# HOMADOS.net
KiCad netlist of a schematic drawn in EAGLE
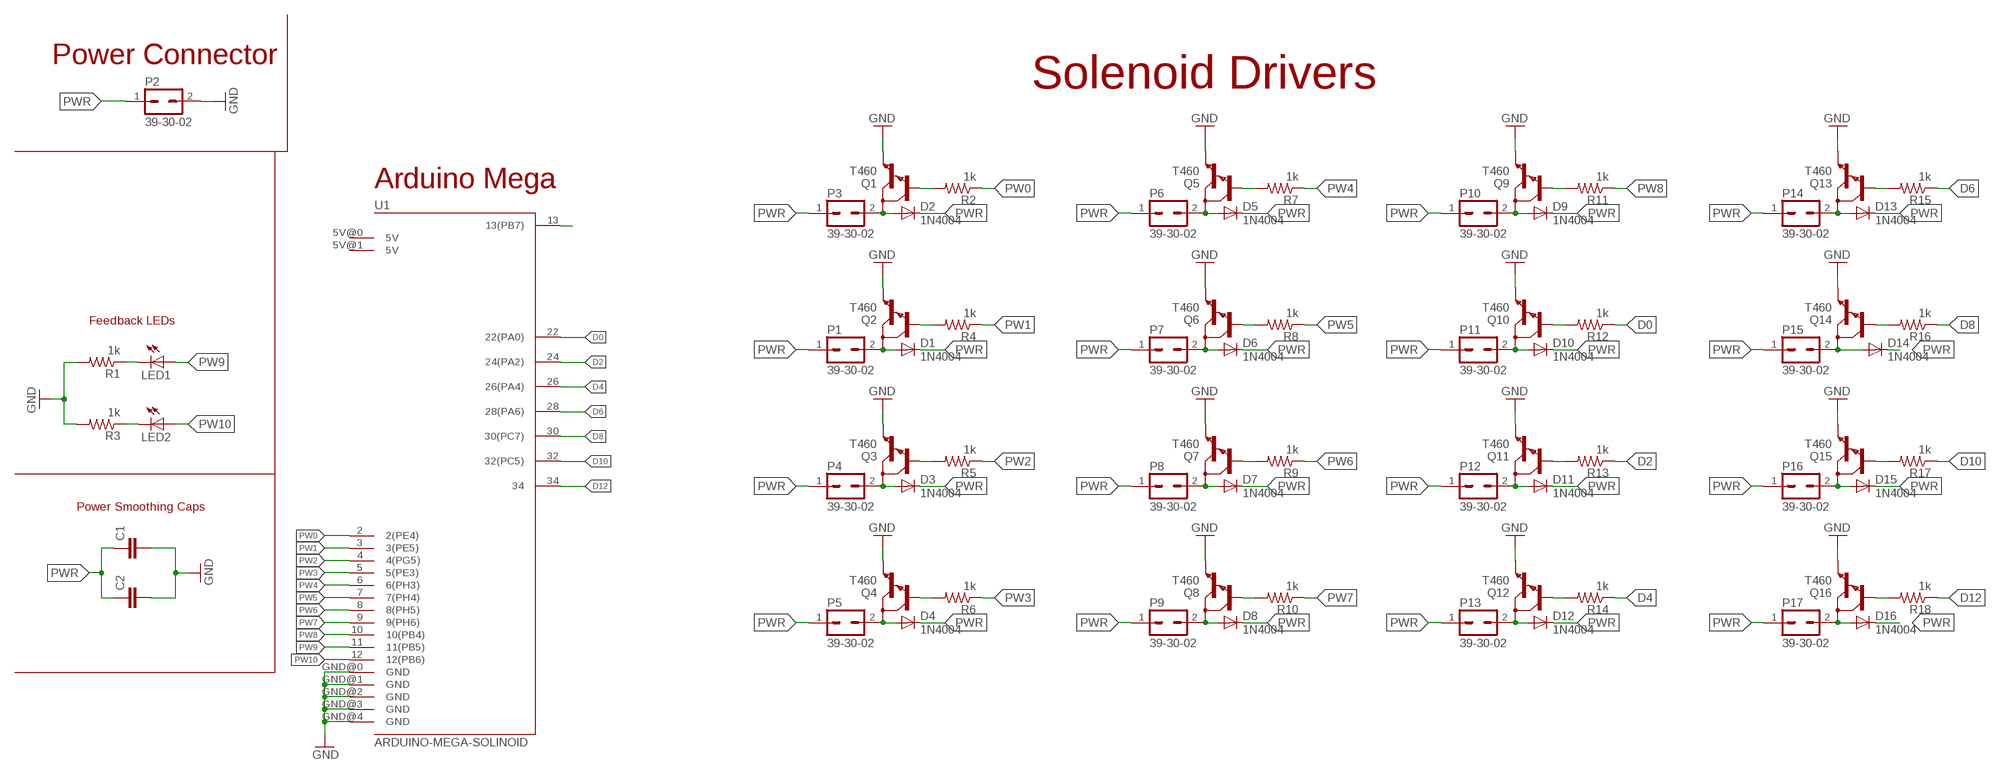
[diagram p0: schematic, sheet 1]

(export (version "E")
  (design (tool "Eeschema 10.0.6"))
  (components
    (comp (ref "C1")
      (value "CAPPTH1")
      (footprint "eagle-import:CAP-PTH-5MM")
      (libsource (lib "eagle-import") (part "CAPPTH1"))
    )
    (comp (ref "C2")
      (value "CAPPTH3")
      (footprint "eagle-import:CAP-PTH-LARGE")
      (libsource (lib "eagle-import") (part "CAPPTH3"))
    )
    (comp (ref "D1")
      (value "1N4004")
      (footprint "eagle-import:DO41-10")
      (libsource (lib "eagle-import") (part "1N4004"))
    )
    (comp (ref "D2")
      (value "1N4004")
      (footprint "eagle-import:DO41-10")
      (libsource (lib "eagle-import") (part "1N4004"))
    )
    (comp (ref "D3")
      (value "1N4004")
      (footprint "eagle-import:DO41-10")
      (libsource (lib "eagle-import") (part "1N4004"))
    )
    (comp (ref "D4")
      (value "1N4004")
      (footprint "eagle-import:DO41-10")
      (libsource (lib "eagle-import") (part "1N4004"))
    )
    (comp (ref "D5")
      (value "1N4004")
      (footprint "eagle-import:DO41-10")
      (libsource (lib "eagle-import") (part "1N4004"))
    )
    (comp (ref "D6")
      (value "1N4004")
      (footprint "eagle-import:DO41-10")
      (libsource (lib "eagle-import") (part "1N4004"))
    )
    (comp (ref "D7")
      (value "1N4004")
      (footprint "eagle-import:DO41-10")
      (libsource (lib "eagle-import") (part "1N4004"))
    )
    (comp (ref "D8")
      (value "1N4004")
      (footprint "eagle-import:DO41-10")
      (libsource (lib "eagle-import") (part "1N4004"))
    )
    (comp (ref "D9")
      (value "1N4004")
      (footprint "eagle-import:DO41-10")
      (libsource (lib "eagle-import") (part "1N4004"))
    )
    (comp (ref "D10")
      (value "1N4004")
      (footprint "eagle-import:DO41-10")
      (libsource (lib "eagle-import") (part "1N4004"))
    )
    (comp (ref "D11")
      (value "1N4004")
      (footprint "eagle-import:DO41-10")
      (libsource (lib "eagle-import") (part "1N4004"))
    )
    (comp (ref "D12")
      (value "1N4004")
      (footprint "eagle-import:DO41-10")
      (libsource (lib "eagle-import") (part "1N4004"))
    )
    (comp (ref "D13")
      (value "1N4004")
      (footprint "eagle-import:DO41-10")
      (libsource (lib "eagle-import") (part "1N4004"))
    )
    (comp (ref "D14")
      (value "1N4004")
      (footprint "eagle-import:DO41-10")
      (libsource (lib "eagle-import") (part "1N4004"))
    )
    (comp (ref "D15")
      (value "1N4004")
      (footprint "eagle-import:DO41-10")
      (libsource (lib "eagle-import") (part "1N4004"))
    )
    (comp (ref "D16")
      (value "1N4004")
      (footprint "eagle-import:DO41-10")
      (libsource (lib "eagle-import") (part "1N4004"))
    )
    (comp (ref "LED1")
      (value "LED5MM")
      (footprint "eagle-import:LED5MM")
      (libsource (lib "eagle-import") (part "LED5MM"))
    )
    (comp (ref "LED2")
      (value "LED5MM")
      (footprint "eagle-import:LED5MM")
      (libsource (lib "eagle-import") (part "LED5MM"))
    )
    (comp (ref "P1")
      (value "39-30-02")
      (footprint "eagle-import:39-30-_02_")
      (libsource (lib "eagle-import") (part "39-30-?02?"))
    )
    (comp (ref "P2")
      (value "39-30-02")
      (footprint "eagle-import:39-30-_02_")
      (libsource (lib "eagle-import") (part "39-30-?02?"))
    )
    (comp (ref "P3")
      (value "39-30-02")
      (footprint "eagle-import:39-30-_02_")
      (libsource (lib "eagle-import") (part "39-30-?02?"))
    )
    (comp (ref "P4")
      (value "39-30-02")
      (footprint "eagle-import:39-30-_02_")
      (libsource (lib "eagle-import") (part "39-30-?02?"))
    )
    (comp (ref "P5")
      (value "39-30-02")
      (footprint "eagle-import:39-30-_02_")
      (libsource (lib "eagle-import") (part "39-30-?02?"))
    )
    (comp (ref "P6")
      (value "39-30-02")
      (footprint "eagle-import:39-30-_02_")
      (libsource (lib "eagle-import") (part "39-30-?02?"))
    )
    (comp (ref "P7")
      (value "39-30-02")
      (footprint "eagle-import:39-30-_02_")
      (libsource (lib "eagle-import") (part "39-30-?02?"))
    )
    (comp (ref "P8")
      (value "39-30-02")
      (footprint "eagle-import:39-30-_02_")
      (libsource (lib "eagle-import") (part "39-30-?02?"))
    )
    (comp (ref "P9")
      (value "39-30-02")
      (footprint "eagle-import:39-30-_02_")
      (libsource (lib "eagle-import") (part "39-30-?02?"))
    )
    (comp (ref "P10")
      (value "39-30-02")
      (footprint "eagle-import:39-30-_02_")
      (libsource (lib "eagle-import") (part "39-30-?02?"))
    )
    (comp (ref "P11")
      (value "39-30-02")
      (footprint "eagle-import:39-30-_02_")
      (libsource (lib "eagle-import") (part "39-30-?02?"))
    )
    (comp (ref "P12")
      (value "39-30-02")
      (footprint "eagle-import:39-30-_02_")
      (libsource (lib "eagle-import") (part "39-30-?02?"))
    )
    (comp (ref "P13")
      (value "39-30-02")
      (footprint "eagle-import:39-30-_02_")
      (libsource (lib "eagle-import") (part "39-30-?02?"))
    )
    (comp (ref "P14")
      (value "39-30-02")
      (footprint "eagle-import:39-30-_02_")
      (libsource (lib "eagle-import") (part "39-30-?02?"))
    )
    (comp (ref "P15")
      (value "39-30-02")
      (footprint "eagle-import:39-30-_02_")
      (libsource (lib "eagle-import") (part "39-30-?02?"))
    )
    (comp (ref "P16")
      (value "39-30-02")
      (footprint "eagle-import:39-30-_02_")
      (libsource (lib "eagle-import") (part "39-30-?02?"))
    )
    (comp (ref "P17")
      (value "39-30-02")
      (footprint "eagle-import:39-30-_02_")
      (libsource (lib "eagle-import") (part "39-30-?02?"))
    )
    (comp (ref "Q1")
      (value "T460")
      (footprint "eagle-import:TO225AAV")
      (libsource (lib "eagle-import") (part "MJE800"))
    )
    (comp (ref "Q2")
      (value "T460")
      (footprint "eagle-import:TO225AAV")
      (libsource (lib "eagle-import") (part "MJE800"))
    )
    (comp (ref "Q3")
      (value "T460")
      (footprint "eagle-import:TO225AAV")
      (libsource (lib "eagle-import") (part "MJE800"))
    )
    (comp (ref "Q4")
      (value "T460")
      (footprint "eagle-import:TO225AAV")
      (libsource (lib "eagle-import") (part "MJE800"))
    )
    (comp (ref "Q5")
      (value "T460")
      (footprint "eagle-import:TO225AAV")
      (libsource (lib "eagle-import") (part "MJE800"))
    )
    (comp (ref "Q6")
      (value "T460")
      (footprint "eagle-import:TO225AAV")
      (libsource (lib "eagle-import") (part "MJE800"))
    )
    (comp (ref "Q7")
      (value "T460")
      (footprint "eagle-import:TO225AAV")
      (libsource (lib "eagle-import") (part "MJE800"))
    )
    (comp (ref "Q8")
      (value "T460")
      (footprint "eagle-import:TO225AAV")
      (libsource (lib "eagle-import") (part "MJE800"))
    )
    (comp (ref "Q9")
      (value "T460")
      (footprint "eagle-import:TO225AAV")
      (libsource (lib "eagle-import") (part "MJE800"))
    )
    (comp (ref "Q10")
      (value "T460")
      (footprint "eagle-import:TO225AAV")
      (libsource (lib "eagle-import") (part "MJE800"))
    )
    (comp (ref "Q11")
      (value "T460")
      (footprint "eagle-import:TO225AAV")
      (libsource (lib "eagle-import") (part "MJE800"))
    )
    (comp (ref "Q12")
      (value "T460")
      (footprint "eagle-import:TO225AAV")
      (libsource (lib "eagle-import") (part "MJE800"))
    )
    (comp (ref "Q13")
      (value "T460")
      (footprint "eagle-import:TO225AAV")
      (libsource (lib "eagle-import") (part "MJE800"))
    )
    (comp (ref "Q14")
      (value "T460")
      (footprint "eagle-import:TO225AAV")
      (libsource (lib "eagle-import") (part "MJE800"))
    )
    (comp (ref "Q15")
      (value "T460")
      (footprint "eagle-import:TO225AAV")
      (libsource (lib "eagle-import") (part "MJE800"))
    )
    (comp (ref "Q16")
      (value "T460")
      (footprint "eagle-import:TO225AAV")
      (libsource (lib "eagle-import") (part "MJE800"))
    )
    (comp (ref "R1")
      (value "1k")
      (footprint "eagle-import:AXIAL-0.3-KIT")
      (libsource (lib "eagle-import") (part "RESISTORKIT"))
    )
    (comp (ref "R2")
      (value "1k")
      (footprint "eagle-import:AXIAL-0.3-KIT")
      (libsource (lib "eagle-import") (part "RESISTORKIT"))
    )
    (comp (ref "R3")
      (value "1k")
      (footprint "eagle-import:AXIAL-0.3-KIT")
      (libsource (lib "eagle-import") (part "RESISTORKIT"))
    )
    (comp (ref "R4")
      (value "1k")
      (footprint "eagle-import:AXIAL-0.3-KIT")
      (libsource (lib "eagle-import") (part "RESISTORKIT"))
    )
    (comp (ref "R5")
      (value "1k")
      (footprint "eagle-import:AXIAL-0.3-KIT")
      (libsource (lib "eagle-import") (part "RESISTORKIT"))
    )
    (comp (ref "R6")
      (value "1k")
      (footprint "eagle-import:AXIAL-0.3-KIT")
      (libsource (lib "eagle-import") (part "RESISTORKIT"))
    )
    (comp (ref "R7")
      (value "1k")
      (footprint "eagle-import:AXIAL-0.3-KIT")
      (libsource (lib "eagle-import") (part "RESISTORKIT"))
    )
    (comp (ref "R8")
      (value "1k")
      (footprint "eagle-import:AXIAL-0.3-KIT")
      (libsource (lib "eagle-import") (part "RESISTORKIT"))
    )
    (comp (ref "R9")
      (value "1k")
      (footprint "eagle-import:AXIAL-0.3-KIT")
      (libsource (lib "eagle-import") (part "RESISTORKIT"))
    )
    (comp (ref "R10")
      (value "1k")
      (footprint "eagle-import:AXIAL-0.3-KIT")
      (libsource (lib "eagle-import") (part "RESISTORKIT"))
    )
    (comp (ref "R11")
      (value "1k")
      (footprint "eagle-import:AXIAL-0.3-KIT")
      (libsource (lib "eagle-import") (part "RESISTORKIT"))
    )
    (comp (ref "R12")
      (value "1k")
      (footprint "eagle-import:AXIAL-0.3-KIT")
      (libsource (lib "eagle-import") (part "RESISTORKIT"))
    )
    (comp (ref "R13")
      (value "1k")
      (footprint "eagle-import:AXIAL-0.3-KIT")
      (libsource (lib "eagle-import") (part "RESISTORKIT"))
    )
    (comp (ref "R14")
      (value "1k")
      (footprint "eagle-import:AXIAL-0.3-KIT")
      (libsource (lib "eagle-import") (part "RESISTORKIT"))
    )
    (comp (ref "R15")
      (value "1k")
      (footprint "eagle-import:AXIAL-0.3-KIT")
      (libsource (lib "eagle-import") (part "RESISTORKIT"))
    )
    (comp (ref "R16")
      (value "1k")
      (footprint "eagle-import:AXIAL-0.3-KIT")
      (libsource (lib "eagle-import") (part "RESISTORKIT"))
    )
    (comp (ref "R17")
      (value "1k")
      (footprint "eagle-import:AXIAL-0.3-KIT")
      (libsource (lib "eagle-import") (part "RESISTORKIT"))
    )
    (comp (ref "R18")
      (value "1k")
      (footprint "eagle-import:AXIAL-0.3-KIT")
      (libsource (lib "eagle-import") (part "RESISTORKIT"))
    )
    (comp (ref "U1")
      (value "ARDUINO-MEGA-SOLINOID")
      (footprint "eagle-import:ARDUINO_MEGA-SOLINOID")
      (libsource (lib "eagle-import") (part "ARDUINO-MEGA-SOLINOID"))
    )
  )
  (nets
    (net (code "1") (name "D0") (class "Default")
      (node (ref "R12") (pin "P$1") (pinfunction "1_P$1") (pintype "passive"))
      (node (ref "U1") (pin "22") (pinfunction "22(PA0)_22") (pintype "bidirectional"))
    )
    (net (code "2") (name "D2") (class "Default")
      (node (ref "R13") (pin "P$1") (pinfunction "1_P$1") (pintype "passive"))
      (node (ref "U1") (pin "24") (pinfunction "24(PA2)_24") (pintype "bidirectional"))
    )
    (net (code "3") (name "D4") (class "Default")
      (node (ref "R14") (pin "P$1") (pinfunction "1_P$1") (pintype "passive"))
      (node (ref "U1") (pin "26") (pinfunction "26(PA4)_26") (pintype "bidirectional"))
    )
    (net (code "4") (name "D6") (class "Default")
      (node (ref "R15") (pin "P$1") (pinfunction "1_P$1") (pintype "passive"))
      (node (ref "U1") (pin "28") (pinfunction "28(PA6)_28") (pintype "bidirectional"))
    )
    (net (code "5") (name "D8") (class "Default")
      (node (ref "R16") (pin "P$1") (pinfunction "1_P$1") (pintype "passive"))
      (node (ref "U1") (pin "30") (pinfunction "30(PC7)_30") (pintype "bidirectional"))
    )
    (net (code "6") (name "D10") (class "Default")
      (node (ref "R17") (pin "P$1") (pinfunction "1_P$1") (pintype "passive"))
      (node (ref "U1") (pin "32") (pinfunction "32(PC5)_32") (pintype "bidirectional"))
    )
    (net (code "7") (name "D12") (class "Default")
      (node (ref "R18") (pin "P$1") (pinfunction "1_P$1") (pintype "passive"))
      (node (ref "U1") (pin "34") (pinfunction "34_34") (pintype "bidirectional"))
    )
    (net (code "8") (name "GND") (class "Default")
      (node (ref "C1") (pin "2") (pinfunction "2_2") (pintype "passive"))
      (node (ref "C2") (pin "2") (pinfunction "2_2") (pintype "passive"))
      (node (ref "P2") (pin "2") (pinfunction "2_2") (pintype "passive"))
      (node (ref "Q1") (pin "1") (pinfunction "E_1") (pintype "passive"))
      (node (ref "Q10") (pin "1") (pinfunction "E_1") (pintype "passive"))
      (node (ref "Q11") (pin "1") (pinfunction "E_1") (pintype "passive"))
      (node (ref "Q12") (pin "1") (pinfunction "E_1") (pintype "passive"))
      (node (ref "Q13") (pin "1") (pinfunction "E_1") (pintype "passive"))
      (node (ref "Q14") (pin "1") (pinfunction "E_1") (pintype "passive"))
      (node (ref "Q15") (pin "1") (pinfunction "E_1") (pintype "passive"))
      (node (ref "Q16") (pin "1") (pinfunction "E_1") (pintype "passive"))
      (node (ref "Q2") (pin "1") (pinfunction "E_1") (pintype "passive"))
      (node (ref "Q3") (pin "1") (pinfunction "E_1") (pintype "passive"))
      (node (ref "Q4") (pin "1") (pinfunction "E_1") (pintype "passive"))
      (node (ref "Q5") (pin "1") (pinfunction "E_1") (pintype "passive"))
      (node (ref "Q6") (pin "1") (pinfunction "E_1") (pintype "passive"))
      (node (ref "Q7") (pin "1") (pinfunction "E_1") (pintype "passive"))
      (node (ref "Q8") (pin "1") (pinfunction "E_1") (pintype "passive"))
      (node (ref "Q9") (pin "1") (pinfunction "E_1") (pintype "passive"))
      (node (ref "R1") (pin "P$2") (pinfunction "2_P$2") (pintype "passive"))
      (node (ref "R3") (pin "P$2") (pinfunction "2_P$2") (pintype "passive"))
      (node (ref "U1") (pin "GND@0") (pinfunction "GND_GND@0") (pintype "bidirectional"))
      (node (ref "U1") (pin "GND@1") (pinfunction "GND_GND@1") (pintype "bidirectional"))
      (node (ref "U1") (pin "GND@2") (pinfunction "GND_GND@2") (pintype "bidirectional"))
      (node (ref "U1") (pin "GND@3") (pinfunction "GND_GND@3") (pintype "bidirectional"))
      (node (ref "U1") (pin "GND@4") (pinfunction "GND_GND@4") (pintype "bidirectional"))
    )
    (net (code "9") (name "Net-(LED1-C)") (class "Default")
      (node (ref "LED1") (pin "K") (pinfunction "C_K") (pintype "passive"))
      (node (ref "R1") (pin "P$1") (pinfunction "1_P$1") (pintype "passive"))
    )
    (net (code "10") (name "Net-(LED2-C)") (class "Default")
      (node (ref "LED2") (pin "K") (pinfunction "C_K") (pintype "passive"))
      (node (ref "R3") (pin "P$1") (pinfunction "1_P$1") (pintype "passive"))
    )
    (net (code "11") (name "Net-(Q1-B)") (class "Default")
      (node (ref "Q1") (pin "3") (pinfunction "B_3") (pintype "passive"))
      (node (ref "R2") (pin "P$2") (pinfunction "2_P$2") (pintype "passive"))
    )
    (net (code "12") (name "Net-(Q1-C)") (class "Default")
      (node (ref "D2") (pin "A") (pinfunction "A_A") (pintype "passive"))
      (node (ref "P3") (pin "2") (pinfunction "2_2") (pintype "passive"))
      (node (ref "Q1") (pin "2") (pinfunction "C_2") (pintype "passive"))
    )
    (net (code "13") (name "Net-(Q2-B)") (class "Default")
      (node (ref "Q2") (pin "3") (pinfunction "B_3") (pintype "passive"))
      (node (ref "R4") (pin "P$2") (pinfunction "2_P$2") (pintype "passive"))
    )
    (net (code "14") (name "Net-(Q2-C)") (class "Default")
      (node (ref "D1") (pin "A") (pinfunction "A_A") (pintype "passive"))
      (node (ref "P1") (pin "2") (pinfunction "2_2") (pintype "passive"))
      (node (ref "Q2") (pin "2") (pinfunction "C_2") (pintype "passive"))
    )
    (net (code "15") (name "Net-(Q3-B)") (class "Default")
      (node (ref "Q3") (pin "3") (pinfunction "B_3") (pintype "passive"))
      (node (ref "R5") (pin "P$2") (pinfunction "2_P$2") (pintype "passive"))
    )
    (net (code "16") (name "Net-(Q3-C)") (class "Default")
      (node (ref "D3") (pin "A") (pinfunction "A_A") (pintype "passive"))
      (node (ref "P4") (pin "2") (pinfunction "2_2") (pintype "passive"))
      (node (ref "Q3") (pin "2") (pinfunction "C_2") (pintype "passive"))
    )
    (net (code "17") (name "Net-(Q4-B)") (class "Default")
      (node (ref "Q4") (pin "3") (pinfunction "B_3") (pintype "passive"))
      (node (ref "R6") (pin "P$2") (pinfunction "2_P$2") (pintype "passive"))
    )
    (net (code "18") (name "Net-(Q4-C)") (class "Default")
      (node (ref "D4") (pin "A") (pinfunction "A_A") (pintype "passive"))
      (node (ref "P5") (pin "2") (pinfunction "2_2") (pintype "passive"))
      (node (ref "Q4") (pin "2") (pinfunction "C_2") (pintype "passive"))
    )
    (net (code "19") (name "Net-(Q5-B)") (class "Default")
      (node (ref "Q5") (pin "3") (pinfunction "B_3") (pintype "passive"))
      (node (ref "R7") (pin "P$2") (pinfunction "2_P$2") (pintype "passive"))
    )
    (net (code "20") (name "Net-(Q5-C)") (class "Default")
      (node (ref "D5") (pin "A") (pinfunction "A_A") (pintype "passive"))
      (node (ref "P6") (pin "2") (pinfunction "2_2") (pintype "passive"))
      (node (ref "Q5") (pin "2") (pinfunction "C_2") (pintype "passive"))
    )
    (net (code "21") (name "Net-(Q6-B)") (class "Default")
      (node (ref "Q6") (pin "3") (pinfunction "B_3") (pintype "passive"))
      (node (ref "R8") (pin "P$2") (pinfunction "2_P$2") (pintype "passive"))
    )
    (net (code "22") (name "Net-(Q6-C)") (class "Default")
      (node (ref "D6") (pin "A") (pinfunction "A_A") (pintype "passive"))
      (node (ref "P7") (pin "2") (pinfunction "2_2") (pintype "passive"))
      (node (ref "Q6") (pin "2") (pinfunction "C_2") (pintype "passive"))
    )
    (net (code "23") (name "Net-(Q7-B)") (class "Default")
      (node (ref "Q7") (pin "3") (pinfunction "B_3") (pintype "passive"))
      (node (ref "R9") (pin "P$2") (pinfunction "2_P$2") (pintype "passive"))
    )
    (net (code "24") (name "Net-(Q7-C)") (class "Default")
      (node (ref "D7") (pin "A") (pinfunction "A_A") (pintype "passive"))
      (node (ref "P8") (pin "2") (pinfunction "2_2") (pintype "passive"))
      (node (ref "Q7") (pin "2") (pinfunction "C_2") (pintype "passive"))
    )
    (net (code "25") (name "Net-(Q8-B)") (class "Default")
      (node (ref "Q8") (pin "3") (pinfunction "B_3") (pintype "passive"))
      (node (ref "R10") (pin "P$2") (pinfunction "2_P$2") (pintype "passive"))
    )
    (net (code "26") (name "Net-(Q8-C)") (class "Default")
      (node (ref "D8") (pin "A") (pinfunction "A_A") (pintype "passive"))
      (node (ref "P9") (pin "2") (pinfunction "2_2") (pintype "passive"))
      (node (ref "Q8") (pin "2") (pinfunction "C_2") (pintype "passive"))
    )
    (net (code "27") (name "Net-(Q9-B)") (class "Default")
      (node (ref "Q9") (pin "3") (pinfunction "B_3") (pintype "passive"))
      (node (ref "R11") (pin "P$2") (pinfunction "2_P$2") (pintype "passive"))
    )
    (net (code "28") (name "Net-(Q9-C)") (class "Default")
      (node (ref "D9") (pin "A") (pinfunction "A_A") (pintype "passive"))
      (node (ref "P10") (pin "2") (pinfunction "2_2") (pintype "passive"))
      (node (ref "Q9") (pin "2") (pinfunction "C_2") (pintype "passive"))
    )
    (net (code "29") (name "Net-(Q10-B)") (class "Default")
      (node (ref "Q10") (pin "3") (pinfunction "B_3") (pintype "passive"))
      (node (ref "R12") (pin "P$2") (pinfunction "2_P$2") (pintype "passive"))
    )
    (net (code "30") (name "Net-(Q10-C)") (class "Default")
      (node (ref "D10") (pin "A") (pinfunction "A_A") (pintype "passive"))
      (node (ref "P11") (pin "2") (pinfunction "2_2") (pintype "passive"))
      (node (ref "Q10") (pin "2") (pinfunction "C_2") (pintype "passive"))
    )
    (net (code "31") (name "Net-(Q11-B)") (class "Default")
      (node (ref "Q11") (pin "3") (pinfunction "B_3") (pintype "passive"))
      (node (ref "R13") (pin "P$2") (pinfunction "2_P$2") (pintype "passive"))
    )
    (net (code "32") (name "Net-(Q11-C)") (class "Default")
      (node (ref "D11") (pin "A") (pinfunction "A_A") (pintype "passive"))
      (node (ref "P12") (pin "2") (pinfunction "2_2") (pintype "passive"))
      (node (ref "Q11") (pin "2") (pinfunction "C_2") (pintype "passive"))
    )
    (net (code "33") (name "Net-(Q12-B)") (class "Default")
      (node (ref "Q12") (pin "3") (pinfunction "B_3") (pintype "passive"))
      (node (ref "R14") (pin "P$2") (pinfunction "2_P$2") (pintype "passive"))
    )
    (net (code "34") (name "Net-(Q12-C)") (class "Default")
      (node (ref "D12") (pin "A") (pinfunction "A_A") (pintype "passive"))
      (node (ref "P13") (pin "2") (pinfunction "2_2") (pintype "passive"))
      (node (ref "Q12") (pin "2") (pinfunction "C_2") (pintype "passive"))
    )
    (net (code "35") (name "Net-(Q13-B)") (class "Default")
      (node (ref "Q13") (pin "3") (pinfunction "B_3") (pintype "passive"))
      (node (ref "R15") (pin "P$2") (pinfunction "2_P$2") (pintype "passive"))
    )
    (net (code "36") (name "Net-(Q13-C)") (class "Default")
      (node (ref "D13") (pin "A") (pinfunction "A_A") (pintype "passive"))
      (node (ref "P14") (pin "2") (pinfunction "2_2") (pintype "passive"))
      (node (ref "Q13") (pin "2") (pinfunction "C_2") (pintype "passive"))
    )
    (net (code "37") (name "Net-(Q14-B)") (class "Default")
      (node (ref "Q14") (pin "3") (pinfunction "B_3") (pintype "passive"))
      (node (ref "R16") (pin "P$2") (pinfunction "2_P$2") (pintype "passive"))
    )
    (net (code "38") (name "Net-(Q14-C)") (class "Default")
      (node (ref "D14") (pin "A") (pinfunction "A_A") (pintype "passive"))
      (node (ref "P15") (pin "2") (pinfunction "2_2") (pintype "passive"))
      (node (ref "Q14") (pin "2") (pinfunction "C_2") (pintype "passive"))
    )
    (net (code "39") (name "Net-(Q15-B)") (class "Default")
      (node (ref "Q15") (pin "3") (pinfunction "B_3") (pintype "passive"))
      (node (ref "R17") (pin "P$2") (pinfunction "2_P$2") (pintype "passive"))
    )
    (net (code "40") (name "Net-(Q15-C)") (class "Default")
      (node (ref "D15") (pin "A") (pinfunction "A_A") (pintype "passive"))
      (node (ref "P16") (pin "2") (pinfunction "2_2") (pintype "passive"))
      (node (ref "Q15") (pin "2") (pinfunction "C_2") (pintype "passive"))
    )
    (net (code "41") (name "Net-(Q16-B)") (class "Default")
      (node (ref "Q16") (pin "3") (pinfunction "B_3") (pintype "passive"))
      (node (ref "R18") (pin "P$2") (pinfunction "2_P$2") (pintype "passive"))
    )
    (net (code "42") (name "Net-(Q16-C)") (class "Default")
      (node (ref "D16") (pin "A") (pinfunction "A_A") (pintype "passive"))
      (node (ref "P17") (pin "2") (pinfunction "2_2") (pintype "passive"))
      (node (ref "Q16") (pin "2") (pinfunction "C_2") (pintype "passive"))
    )
    (net (code "43") (name "PW0") (class "Default")
      (node (ref "R2") (pin "P$1") (pinfunction "1_P$1") (pintype "passive"))
      (node (ref "U1") (pin "2") (pinfunction "2(PE4)_2") (pintype "bidirectional"))
    )
    (net (code "44") (name "PW1") (class "Default")
      (node (ref "R4") (pin "P$1") (pinfunction "1_P$1") (pintype "passive"))
      (node (ref "U1") (pin "3") (pinfunction "3(PE5)_3") (pintype "bidirectional"))
    )
    (net (code "45") (name "PW2") (class "Default")
      (node (ref "R5") (pin "P$1") (pinfunction "1_P$1") (pintype "passive"))
      (node (ref "U1") (pin "4") (pinfunction "4(PG5)_4") (pintype "bidirectional"))
    )
    (net (code "46") (name "PW3") (class "Default")
      (node (ref "R6") (pin "P$1") (pinfunction "1_P$1") (pintype "passive"))
      (node (ref "U1") (pin "5") (pinfunction "5(PE3)_5") (pintype "bidirectional"))
    )
    (net (code "47") (name "PW4") (class "Default")
      (node (ref "R7") (pin "P$1") (pinfunction "1_P$1") (pintype "passive"))
      (node (ref "U1") (pin "6") (pinfunction "6(PH3)_6") (pintype "bidirectional"))
    )
    (net (code "48") (name "PW5") (class "Default")
      (node (ref "R8") (pin "P$1") (pinfunction "1_P$1") (pintype "passive"))
      (node (ref "U1") (pin "7") (pinfunction "7(PH4)_7") (pintype "bidirectional"))
    )
    (net (code "49") (name "PW6") (class "Default")
      (node (ref "R9") (pin "P$1") (pinfunction "1_P$1") (pintype "passive"))
      (node (ref "U1") (pin "8") (pinfunction "8(PH5)_8") (pintype "bidirectional"))
    )
    (net (code "50") (name "PW7") (class "Default")
      (node (ref "R10") (pin "P$1") (pinfunction "1_P$1") (pintype "passive"))
      (node (ref "U1") (pin "9") (pinfunction "9(PH6)_9") (pintype "bidirectional"))
    )
    (net (code "51") (name "PW8") (class "Default")
      (node (ref "R11") (pin "P$1") (pinfunction "1_P$1") (pintype "passive"))
      (node (ref "U1") (pin "10") (pinfunction "10(PB4)_10") (pintype "bidirectional"))
    )
    (net (code "52") (name "PW9") (class "Default")
      (node (ref "LED1") (pin "A") (pinfunction "A_A") (pintype "passive"))
      (node (ref "U1") (pin "11") (pinfunction "11(PB5)_11") (pintype "bidirectional"))
    )
    (net (code "53") (name "PW10") (class "Default")
      (node (ref "LED2") (pin "A") (pinfunction "A_A") (pintype "passive"))
      (node (ref "U1") (pin "12") (pinfunction "12(PB6)_12") (pintype "bidirectional"))
    )
    (net (code "54") (name "PWR") (class "Default")
      (node (ref "C1") (pin "1") (pinfunction "1_1") (pintype "passive"))
      (node (ref "C2") (pin "1") (pinfunction "1_1") (pintype "passive"))
      (node (ref "D1") (pin "C") (pinfunction "C_C") (pintype "passive"))
      (node (ref "D10") (pin "C") (pinfunction "C_C") (pintype "passive"))
      (node (ref "D11") (pin "C") (pinfunction "C_C") (pintype "passive"))
      (node (ref "D12") (pin "C") (pinfunction "C_C") (pintype "passive"))
      (node (ref "D13") (pin "C") (pinfunction "C_C") (pintype "passive"))
      (node (ref "D14") (pin "C") (pinfunction "C_C") (pintype "passive"))
      (node (ref "D15") (pin "C") (pinfunction "C_C") (pintype "passive"))
      (node (ref "D16") (pin "C") (pinfunction "C_C") (pintype "passive"))
      (node (ref "D2") (pin "C") (pinfunction "C_C") (pintype "passive"))
      (node (ref "D3") (pin "C") (pinfunction "C_C") (pintype "passive"))
      (node (ref "D4") (pin "C") (pinfunction "C_C") (pintype "passive"))
      (node (ref "D5") (pin "C") (pinfunction "C_C") (pintype "passive"))
      (node (ref "D6") (pin "C") (pinfunction "C_C") (pintype "passive"))
      (node (ref "D7") (pin "C") (pinfunction "C_C") (pintype "passive"))
      (node (ref "D8") (pin "C") (pinfunction "C_C") (pintype "passive"))
      (node (ref "D9") (pin "C") (pinfunction "C_C") (pintype "passive"))
      (node (ref "P1") (pin "1") (pinfunction "1_1") (pintype "passive"))
      (node (ref "P10") (pin "1") (pinfunction "1_1") (pintype "passive"))
      (node (ref "P11") (pin "1") (pinfunction "1_1") (pintype "passive"))
      (node (ref "P12") (pin "1") (pinfunction "1_1") (pintype "passive"))
      (node (ref "P13") (pin "1") (pinfunction "1_1") (pintype "passive"))
      (node (ref "P14") (pin "1") (pinfunction "1_1") (pintype "passive"))
      (node (ref "P15") (pin "1") (pinfunction "1_1") (pintype "passive"))
      (node (ref "P16") (pin "1") (pinfunction "1_1") (pintype "passive"))
      (node (ref "P17") (pin "1") (pinfunction "1_1") (pintype "passive"))
      (node (ref "P2") (pin "1") (pinfunction "1_1") (pintype "passive"))
      (node (ref "P3") (pin "1") (pinfunction "1_1") (pintype "passive"))
      (node (ref "P4") (pin "1") (pinfunction "1_1") (pintype "passive"))
      (node (ref "P5") (pin "1") (pinfunction "1_1") (pintype "passive"))
      (node (ref "P6") (pin "1") (pinfunction "1_1") (pintype "passive"))
      (node (ref "P7") (pin "1") (pinfunction "1_1") (pintype "passive"))
      (node (ref "P8") (pin "1") (pinfunction "1_1") (pintype "passive"))
      (node (ref "P9") (pin "1") (pinfunction "1_1") (pintype "passive"))
    )
    (net (code "55") (name "unconnected-(U1-5V-Pad5V@0)") (class "Default")
      (node (ref "U1") (pin "5V@0") (pinfunction "5V_5V@0") (pintype "bidirectional"))
    )
    (net (code "56") (name "unconnected-(U1-5V-Pad5V@1)") (class "Default")
      (node (ref "U1") (pin "5V@1") (pinfunction "5V_5V@1") (pintype "bidirectional"))
    )
    (net (code "57") (name "unconnected-(U1-13(PB7)-Pad13)") (class "Default")
      (node (ref "U1") (pin "13") (pinfunction "13(PB7)_13") (pintype "bidirectional"))
    )
  )
)
